# Project_by_Andrei_and_Javad.net
KiCad netlist of a schematic drawn in EAGLE
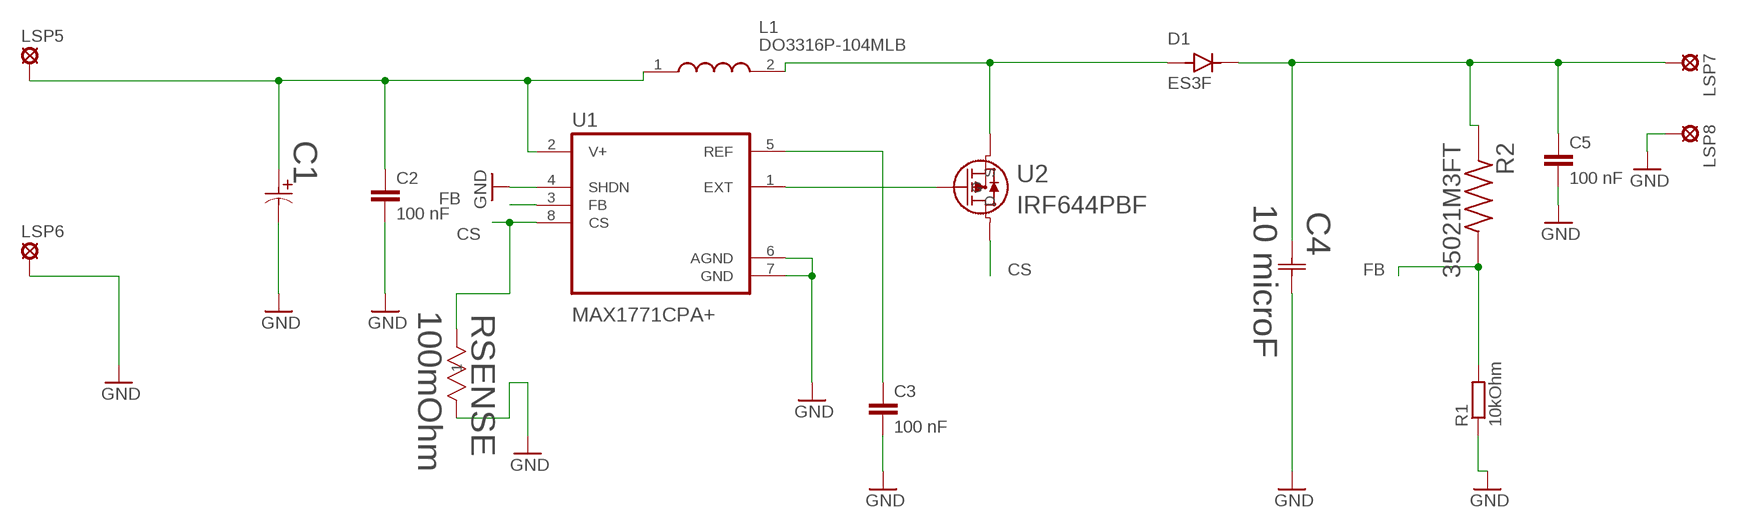
[diagram p0: schematic, sheet 1]

(export (version "E")
  (design (tool "Eeschema 10.0.6"))
  (components
    (comp (ref "C1")
      (value "100 microF")
      (footprint "eagle-import:CAPMP7.6X4.3_4.3N_KEM")
      (fields
        (field (name "MANUFACTURER_PART_NUMBER") "T510X107K020ATE035")
        (field (name "COPYRIGHT") "Copyright (C) 2022 Ultra Librarian. All rights reserved.")
      )
      (libsource (lib "eagle-import") (part "T510X107K020ATE035"))
    )
    (comp (ref "C2")
      (value "100 nF")
      (footprint "eagle-import:C0805")
      (libsource (lib "eagle-import") (part "C-EUC0805"))
    )
    (comp (ref "C3")
      (value "100 nF")
      (footprint "eagle-import:C0805")
      (libsource (lib "eagle-import") (part "C-EUC0805"))
    )
    (comp (ref "C4")
      (value "10 microF")
      (footprint "eagle-import:CAP_EB_G17_PAN")
      (fields
        (field (name "MANUFACTURER_PART_NUMBER") "EEV-EB2E100Q")
        (field (name "COPYRIGHT") "Copyright (C) 2022 Ultra Librarian. All rights reserved.")
      )
      (libsource (lib "eagle-import") (part "EEV-EB2E100Q"))
    )
    (comp (ref "C5")
      (value "100 nF")
      (footprint "eagle-import:C1206")
      (libsource (lib "eagle-import") (part "C-EUC1206"))
    )
    (comp (ref "D1")
      (value "ES3F")
      (footprint "eagle-import:DIOM6859X262N")
      (fields (field (name "MF") "Taiwan Semiconductor"))
      (libsource (lib "eagle-import") (part "ES3F"))
    )
    (comp (ref "L1")
      (value "DO3316P-104MLB")
      (footprint "eagle-import:DO3316P102MLB")
      (fields (field (name "MOUSER_PART_NUMBER") "994-DO3316P-104MLB"))
      (libsource (lib "eagle-import") (part "DO3316P-104MLB"))
    )
    (comp (ref "LSP5")
      (value "LSP13")
      (footprint "eagle-import:LSP13")
      (libsource (lib "eagle-import") (part "LSP13"))
    )
    (comp (ref "LSP6")
      (value "LSP13")
      (footprint "eagle-import:LSP13")
      (libsource (lib "eagle-import") (part "LSP13"))
    )
    (comp (ref "LSP7")
      (value "LSP13")
      (footprint "eagle-import:LSP13")
      (libsource (lib "eagle-import") (part "LSP13"))
    )
    (comp (ref "LSP8")
      (value "LSP13")
      (footprint "eagle-import:LSP13")
      (libsource (lib "eagle-import") (part "LSP13"))
    )
    (comp (ref "R1")
      (value "10kOhm")
      (footprint "eagle-import:R0805")
      (libsource (lib "eagle-import") (part "R-EU_R0805"))
    )
    (comp (ref "R2")
      (value "35021M3FT")
      (footprint "eagle-import:RESC5025X120N")
      (fields (field (name "COMMENT") "4-2176398-9") (field (name "MF") "TE Connectivity"))
      (libsource (lib "eagle-import") (part "35021M3FT"))
    )
    (comp (ref "RSENSE")
      (value "100mOhm")
      (footprint "eagle-import:YAG_R2512_YAG")
      (fields
        (field (name "MANUFACTURER_PART_NUMBER") "RL2512FK-070R1L")
        (field (name "COPYRIGHT") "Copyright (C) 2022 Ultra Librarian. All rights reserved.")
      )
      (libsource (lib "eagle-import") (part "RL2512FK-070R1L"))
    )
    (comp (ref "U1")
      (value "MAX1771CPA+")
      (footprint "eagle-import:DIP794W47P254L991H457Q8")
      (fields (field (name "MF") "Maxim Integrated"))
      (libsource (lib "eagle-import") (part "MAX1771CPA+"))
    )
    (comp (ref "U2")
      (value "IRF644PBF")
      (footprint "eagle-import:TO220AB_VIS")
      (fields (field (name "COPYRIGHT") "Copyright (C) 2022 Ultra Librarian. All rights reserved."))
      (libsource (lib "eagle-import") (part "IRF644PBF"))
    )
  )
  (nets
    (net (code "1") (name "/CS") (class "Default")
      (node (ref "RSENSE") (pin "1") (pinfunction "1_1") (pintype "passive"))
      (node (ref "U1") (pin "8") (pinfunction "CS_8") (pintype "input"))
      (node (ref "U2") (pin "2") (pinfunction "D_2") (pintype "passive"))
    )
    (net (code "2") (name "/FB") (class "Default")
      (node (ref "R1") (pin "2") (pinfunction "2_2") (pintype "passive"))
      (node (ref "R2") (pin "2") (pinfunction "2_2") (pintype "passive"))
      (node (ref "U1") (pin "3") (pinfunction "FB_3") (pintype "input"))
    )
    (net (code "3") (name "GND") (class "Default")
      (node (ref "C1") (pin "2") (pinfunction "2_2") (pintype "passive"))
      (node (ref "C2") (pin "2") (pinfunction "2_2") (pintype "passive"))
      (node (ref "C3") (pin "2") (pinfunction "2_2") (pintype "passive"))
      (node (ref "C4") (pin "2") (pinfunction "2_2") (pintype "passive"))
      (node (ref "C5") (pin "2") (pinfunction "2_2") (pintype "passive"))
      (node (ref "LSP6") (pin "MP") (pinfunction "MP_MP") (pintype "passive"))
      (node (ref "LSP8") (pin "MP") (pinfunction "MP_MP") (pintype "passive"))
      (node (ref "R1") (pin "1") (pinfunction "1_1") (pintype "passive"))
      (node (ref "RSENSE") (pin "2") (pinfunction "2_2") (pintype "passive"))
      (node (ref "U1") (pin "4") (pinfunction "SHDN_4") (pintype "input"))
      (node (ref "U1") (pin "6") (pinfunction "AGND_6") (pintype "power_in"))
      (node (ref "U1") (pin "7") (pinfunction "GND_7") (pintype "power_in"))
    )
    (net (code "4") (name "Net-(D1-K)") (class "Default")
      (node (ref "C4") (pin "1") (pinfunction "1_1") (pintype "passive"))
      (node (ref "C5") (pin "1") (pinfunction "1_1") (pintype "passive"))
      (node (ref "D1") (pin "C") (pinfunction "K_C") (pintype "passive"))
      (node (ref "LSP7") (pin "MP") (pinfunction "MP_MP") (pintype "passive"))
      (node (ref "R2") (pin "1") (pinfunction "1_1") (pintype "passive"))
    )
    (net (code "5") (name "Net-(U1-EXT)") (class "Default")
      (node (ref "U1") (pin "1") (pinfunction "EXT_1") (pintype "output"))
      (node (ref "U2") (pin "1") (pinfunction "G_1") (pintype "passive"))
    )
    (net (code "6") (name "Net-(U1-REF)") (class "Default")
      (node (ref "C3") (pin "1") (pinfunction "1_1") (pintype "passive"))
      (node (ref "U1") (pin "5") (pinfunction "REF_5") (pintype "output"))
    )
    (net (code "7") (name "Net-(U1-V+)") (class "Default")
      (node (ref "C1") (pin "1") (pinfunction "1_1") (pintype "passive"))
      (node (ref "C2") (pin "1") (pinfunction "1_1") (pintype "passive"))
      (node (ref "L1") (pin "1") (pinfunction "1_1") (pintype "bidirectional"))
      (node (ref "LSP5") (pin "MP") (pinfunction "MP_MP") (pintype "passive"))
      (node (ref "U1") (pin "2") (pinfunction "V+_2") (pintype "input"))
    )
    (net (code "8") (name "Net-(U2-S)") (class "Default")
      (node (ref "D1") (pin "A") (pinfunction "A_A") (pintype "passive"))
      (node (ref "L1") (pin "2") (pinfunction "2_2") (pintype "bidirectional"))
      (node (ref "U2") (pin "3") (pinfunction "S_3") (pintype "passive"))
    )
  )
)
